# UART-to-USB.net
KiCad netlist of a schematic drawn in Altium Designer
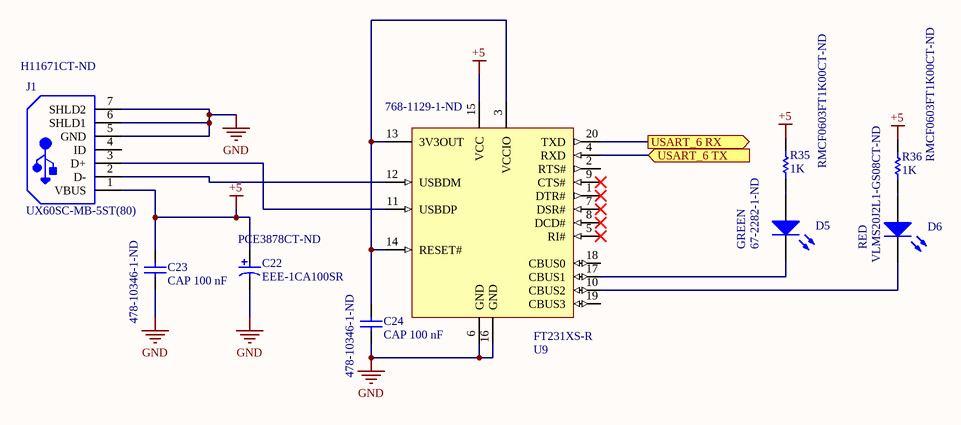
[diagram p0: UART-to-USB.SchDoc]

(export (version "E")
  (design (tool "Eeschema 10.0.6"))
  (components
    (comp (ref "C22")
      (value "EEE-1CA100SR")
      (footprint "PNSC-EEE1CA100SR_L")
      (description "Aluminum Electrolytic Capacitor, 10 uF, +/- 20%, -40 to 85 degC, 2-Pin SMD, RoHS, Tape and Reel")
      (fields
        (field (name "MANUFACTURER") "Panasonic")
        (field (name "SUPPLIER PART NUMBER 1") "PCE3878CT-ND")
      )
      (libsource (lib "Altium Content Vault") (part "CAP-P-2"))
    )
    (comp (ref "C23")
      (value "CAP 100 nF")
      (footprint "06035C104KAT4A")
      (description "Capacitor")
      (fields
        (field (name "SUPPLIER PART NUMBER 1") "478-10346-1-ND")
        (field (name "PUBLISHER") "Altium Limited")
      )
      (libsource (lib "Miscellaneous Devices") (part "Cap"))
    )
    (comp (ref "C24")
      (value "CAP 100 nF")
      (footprint "06035C104KAT4A")
      (description "Capacitor")
      (fields
        (field (name "SUPPLIER PART NUMBER 1") "478-10346-1-ND")
        (field (name "PUBLISHER") "Altium Limited")
      )
      (libsource (lib "Miscellaneous Devices") (part "Cap"))
    )
    (comp (ref "D5")
      (value "GREEN")
      (footprint "Vishay VLMx20 Low Current Mini SMD LED")
      (description "Typical RED, GREEN, YELLOW, AMBER GaAs LED")
      (fields
        (field (name "SUPPLIER PART NUMBER 1") "67-2282-1-ND")
        (field (name "PUBLISHER") "Altium Limited")
      )
      (libsource (lib "Miscellaneous Devices") (part "LED2"))
    )
    (comp (ref "D6")
      (value "RED")
      (footprint "Vishay VLMx20 Low Current Mini SMD LED")
      (description "Typical RED, GREEN, YELLOW, AMBER GaAs LED")
      (fields
        (field (name "SUPPLIER PART NUMBER 1") "VLMS20J2L1-GS08CT-ND")
        (field (name "PUBLISHER") "Altium Limited")
      )
      (libsource (lib "Miscellaneous Devices") (part "LED2"))
    )
    (comp (ref "J1")
      (value "UX60SC-MB-5ST(80)")
      (footprint "HIRO-UX60SC-MB-5ST(80)_V")
      (fields
        (field (name "MANUFACTURER") "Hirose Electric")
        (field (name "SUPPLIER PART NUMBER 1") "H11671CT-ND")
      )
      (libsource (lib "Altium Content Vault") (part "USB-5-2SHLD"))
    )
    (comp (ref "R35")
      (value "1K")
      (footprint "CR0603-J/-000ELF")
      (description "Resistor")
      (fields
        (field (name "SUPPLIER PART NUMBER 1") "RMCF0603FT1K00CT-ND")
        (field (name "PUBLISHER") "Altium Limited")
      )
      (libsource (lib "V2_UMRT_FlightComputer_Prototype_2019") (part "Res1"))
    )
    (comp (ref "R36")
      (value "1K")
      (footprint "CR0603-J/-000ELF")
      (description "Resistor")
      (fields
        (field (name "SUPPLIER PART NUMBER 1") "RMCF0603FT1K00CT-ND")
        (field (name "PUBLISHER") "Altium Limited")
      )
      (libsource (lib "V2_UMRT_FlightComputer_Prototype_2019") (part "Res1"))
    )
    (comp (ref "U9")
      (value "FT231XS-R")
      (footprint "SSOP-20_L")
      (fields (field (name "MANUFACTURER") "FTDI") (field (name "SUPPLIER PART NUMBER 1") "768-1129-1-ND"))
      (libsource (lib "Altium Content Vault") (part "COM-USB-FT231XS-IL20"))
    )
  )
  (nets
    (net (code "1") (name "+5") (class "Default")
      (node (ref "C22") (pin "1") (pinfunction "1_1") (pintype "passive"))
      (node (ref "C23") (pin "1") (pinfunction "1_1") (pintype "passive"))
      (node (ref "J1") (pin "1") (pinfunction "VBUS_1") (pintype "passive"))
      (node (ref "R35") (pin "2") (pinfunction "2_2") (pintype "passive"))
      (node (ref "R36") (pin "2") (pinfunction "2_2") (pintype "passive"))
      (node (ref "U9") (pin "15") (pinfunction "VCC_15") (pintype "power_in"))
    )
    (net (code "2") (name "/USART_6 RX") (class "Default")
      (node (ref "U9") (pin "20") (pinfunction "TXD_20") (pintype "output"))
    )
    (net (code "3") (name "/USART_6 TX") (class "Default")
      (node (ref "U9") (pin "4") (pinfunction "RXD_4") (pintype "input"))
    )
    (net (code "4") (name "GND") (class "Default")
      (node (ref "C22") (pin "2") (pinfunction "2_2") (pintype "passive"))
      (node (ref "C23") (pin "2") (pinfunction "2_2") (pintype "passive"))
      (node (ref "C24") (pin "2") (pinfunction "2_2") (pintype "passive"))
      (node (ref "J1") (pin "5") (pinfunction "GND_5") (pintype "passive"))
      (node (ref "J1") (pin "6") (pinfunction "SHLD1_6") (pintype "passive"))
      (node (ref "J1") (pin "7") (pinfunction "SHLD2_7") (pintype "passive"))
      (node (ref "U9") (pin "16") (pinfunction "GND_16") (pintype "power_in"))
      (node (ref "U9") (pin "6") (pinfunction "GND_6") (pintype "power_in"))
    )
    (net (code "5") (name "Net-(D5-A)") (class "Default")
      (node (ref "D5") (pin "1") (pinfunction "A_1") (pintype "passive"))
      (node (ref "R35") (pin "1") (pinfunction "1_1") (pintype "passive"))
    )
    (net (code "6") (name "Net-(D5-K)") (class "Default")
      (node (ref "D5") (pin "2") (pinfunction "K_2") (pintype "passive"))
      (node (ref "U9") (pin "17") (pinfunction "CBUS1_17") (pintype "bidirectional"))
    )
    (net (code "7") (name "Net-(D6-A)") (class "Default")
      (node (ref "D6") (pin "1") (pinfunction "A_1") (pintype "passive"))
      (node (ref "R36") (pin "1") (pinfunction "1_1") (pintype "passive"))
    )
    (net (code "8") (name "Net-(D6-K)") (class "Default")
      (node (ref "D6") (pin "2") (pinfunction "K_2") (pintype "passive"))
      (node (ref "U9") (pin "10") (pinfunction "CBUS2_10") (pintype "bidirectional"))
    )
    (net (code "9") (name "Net-(J1-D+)") (class "Default")
      (node (ref "J1") (pin "3") (pinfunction "D+_3") (pintype "passive"))
      (node (ref "U9") (pin "11") (pinfunction "USBDP_11") (pintype "input"))
    )
    (net (code "10") (name "Net-(J1-D-)") (class "Default")
      (node (ref "J1") (pin "2") (pinfunction "D-_2") (pintype "passive"))
      (node (ref "U9") (pin "12") (pinfunction "USBDM_12") (pintype "input"))
    )
    (net (code "11") (name "Net-(U9-3V3OUT)") (class "Default")
      (node (ref "C24") (pin "1") (pinfunction "1_1") (pintype "passive"))
      (node (ref "U9") (pin "13") (pinfunction "3V3OUT_13") (pintype "power_in"))
      (node (ref "U9") (pin "14") (pinfunction "RESET#_14") (pintype "input"))
      (node (ref "U9") (pin "3") (pinfunction "VCCIO_3") (pintype "power_in"))
    )
    (net (code "12") (name "unconnected-(J1-ID-Pad4)") (class "Default")
      (node (ref "J1") (pin "4") (pinfunction "ID_4") (pintype "passive"))
    )
    (net (code "13") (name "unconnected-(U9-CBUS0-Pad18)") (class "Default")
      (node (ref "U9") (pin "18") (pinfunction "CBUS0_18") (pintype "bidirectional"))
    )
    (net (code "14") (name "unconnected-(U9-CBUS3-Pad19)") (class "Default")
      (node (ref "U9") (pin "19") (pinfunction "CBUS3_19") (pintype "bidirectional"))
    )
    (net (code "15") (name "unconnected-(U9-CTS#-Pad9)") (class "Default")
      (node (ref "U9") (pin "9") (pinfunction "CTS#_9") (pintype "input+no_connect"))
    )
    (net (code "16") (name "unconnected-(U9-DCD#-Pad8)") (class "Default")
      (node (ref "U9") (pin "8") (pinfunction "DCD#_8") (pintype "input+no_connect"))
    )
    (net (code "17") (name "unconnected-(U9-DSR#-Pad7)") (class "Default")
      (node (ref "U9") (pin "7") (pinfunction "DSR#_7") (pintype "input+no_connect"))
    )
    (net (code "18") (name "unconnected-(U9-DTR#-Pad1)") (class "Default")
      (node (ref "U9") (pin "1") (pinfunction "DTR#_1") (pintype "output+no_connect"))
    )
    (net (code "19") (name "unconnected-(U9-RI#-Pad5)") (class "Default")
      (node (ref "U9") (pin "5") (pinfunction "RI#_5") (pintype "input+no_connect"))
    )
    (net (code "20") (name "unconnected-(U9-RTS#-Pad2)") (class "Default")
      (node (ref "U9") (pin "2") (pinfunction "RTS#_2") (pintype "output"))
    )
  )
)
